# EE464_SCH.net
KiCad netlist of a schematic drawn in Altium Designer
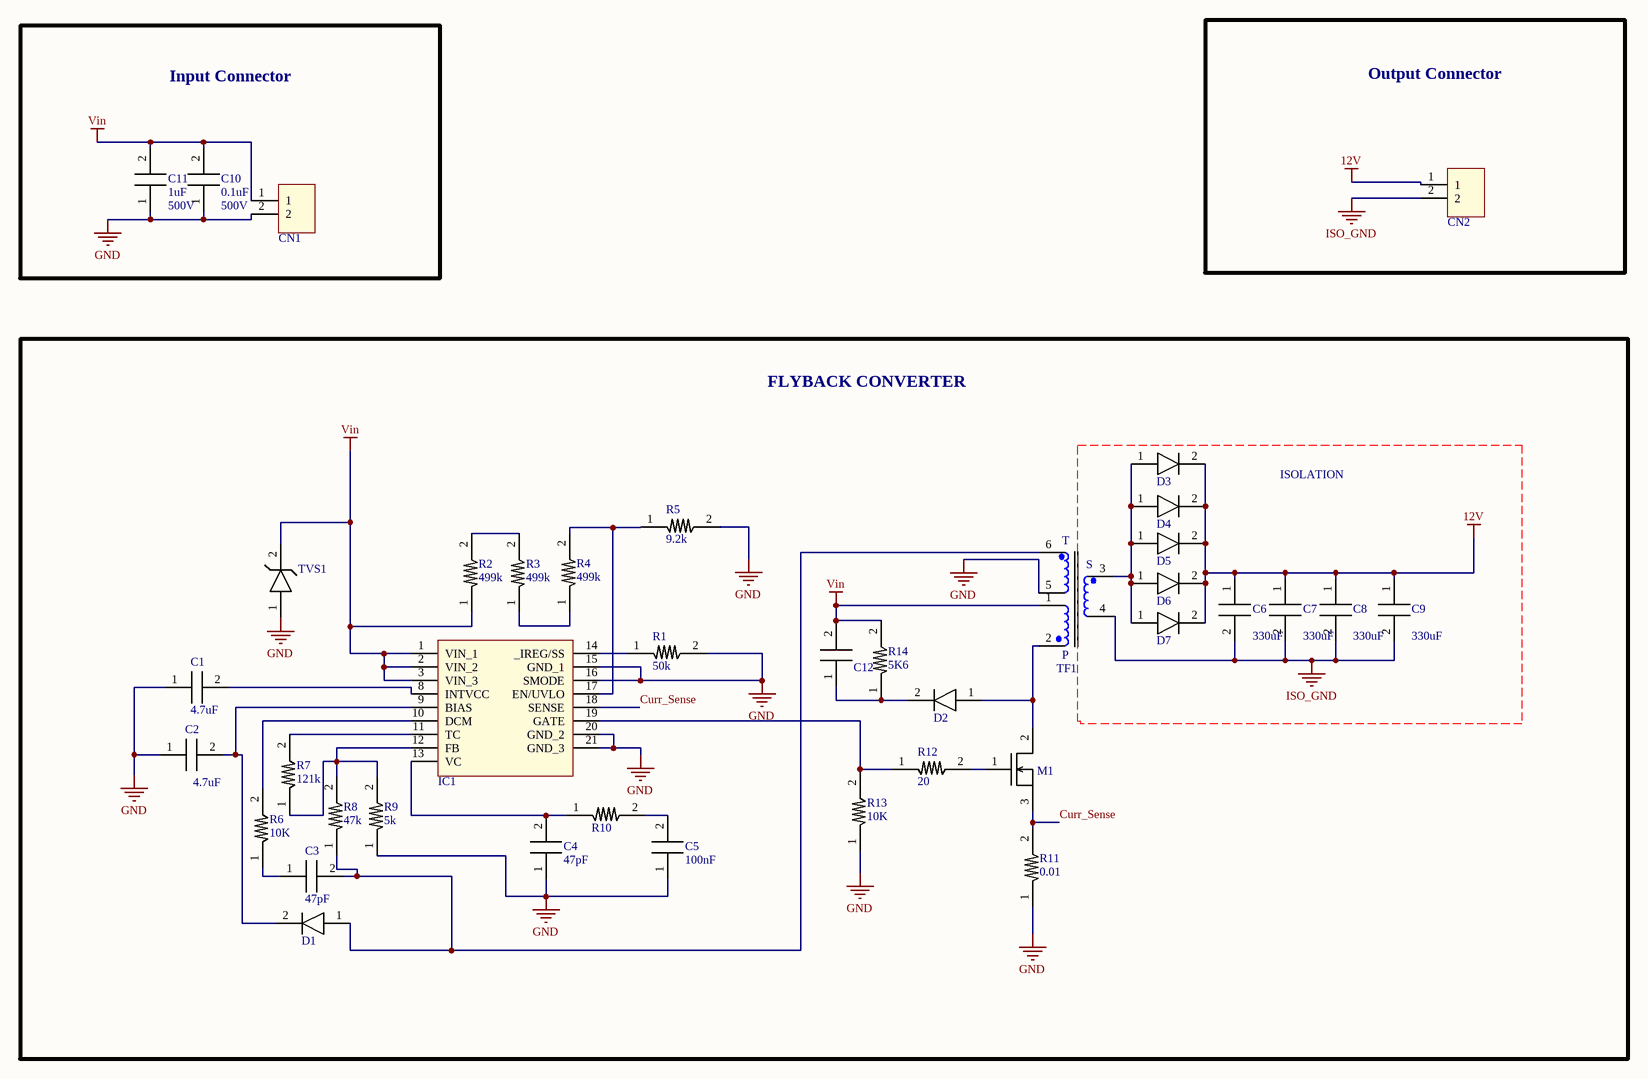
[diagram p0: EE464_SCH.SchDoc]

(export (version "E")
  (design (tool "Eeschema 10.0.6"))
  (components
    (comp (ref "C1")
      (value "CAP 4.7uF 1206")
      (footprint "CAP_1206")
      (fields (field (name "PARAMETER 1") "4.7uF"))
      (libsource (lib "Schlib1") (part "CAP 4.7uF 1206"))
    )
    (comp (ref "C2")
      (value "CAP 4.7uF 1206")
      (footprint "CAP_1206")
      (fields (field (name "PARAMETER 1") "4.7uF"))
      (libsource (lib "Schlib1") (part "CAP 4.7uF 1206"))
    )
    (comp (ref "C3")
      (value "CAP 47pF 0603")
      (footprint "0603_CAP")
      (fields (field (name "PARAMETER 1") "47pF"))
      (libsource (lib "Schlib1") (part "CAP 47pF 0603"))
    )
    (comp (ref "C4")
      (value "CAP 47pF 0603")
      (footprint "0603_CAP")
      (fields (field (name "PARAMETER 1") "47pF"))
      (libsource (lib "Schlib1") (part "CAP 47pF 0603"))
    )
    (comp (ref "C5")
      (value "CAP 100nF")
      (footprint "0603_CAP")
      (fields (field (name "PARAMETER 1") "100nF"))
      (libsource (lib "Schlib1") (part "CAP 100nF"))
    )
    (comp (ref "C6")
      (value "A750KK337M1CAAE014")
      (footprint "CAPPRD350W65D800H900")
      (description "CAP,330uF,AL.POLY.,16V, A750KK337M1CAAE014")
      (fields (field (name "PARAMETER 1") "330uF"))
      (libsource (lib "Schlib1") (part "CAP 330uF AL. POLY."))
    )
    (comp (ref "C7")
      (value "A750KK337M1CAAE014")
      (footprint "CAPPRD350W65D800H900")
      (description "CAP,330uF,AL.POLY.,16V, A750KK337M1CAAE014")
      (fields (field (name "PARAMETER 1") "330uF"))
      (libsource (lib "Schlib1") (part "CAP 330uF AL. POLY."))
    )
    (comp (ref "C8")
      (value "A750KK337M1CAAE014")
      (footprint "CAPPRD350W65D800H900")
      (description "CAP,330uF,AL.POLY.,16V, A750KK337M1CAAE014")
      (fields (field (name "PARAMETER 1") "330uF"))
      (libsource (lib "Schlib1") (part "CAP 330uF AL. POLY."))
    )
    (comp (ref "C9")
      (value "A750KK337M1CAAE014")
      (footprint "CAPPRD350W65D800H900")
      (description "CAP,330uF,AL.POLY.,16V, A750KK337M1CAAE014")
      (fields (field (name "PARAMETER 1") "330uF"))
      (libsource (lib "Schlib1") (part "CAP 330uF AL. POLY."))
    )
    (comp (ref "C10")
      (value "CAP 0.1uF 500V 1210")
      (footprint "CAP_1210")
      (fields (field (name "PARAMETER 1") "0.1uF") (field (name "PARAMETER 2") "500V"))
      (libsource (lib "Schlib1") (part "CAP 0.1uF 500V 1210"))
    )
    (comp (ref "C11")
      (value "CAP 1uF 500v")
      (footprint "CAP_2210")
      (fields (field (name "PARAMETER 1") "1uF") (field (name "PARAMETER 2") "500V"))
      (libsource (lib "Schlib1") (part "CAP 1uF 500v"))
    )
    (comp (ref "C12")
      (value "CAP, 0.1u, 200V, 1206")
      (footprint "CAP_1206")
      (libsource (lib "Schlib1") (part "CAP, 0.1u, 200V, 1206"))
    )
    (comp (ref "CN1")
      (value "CONN_KLE_2_HV")
      (footprint "2828582")
      (libsource (lib "Schlib1") (part "CONN_KLE_2_HV"))
    )
    (comp (ref "CN2")
      (value "CONN_KLE_2_LV")
      (footprint "691103110002")
      (libsource (lib "Schlib1") (part "CONN_KLE_2_LV"))
    )
    (comp (ref "D1")
      (value "DI SK115")
      (footprint "DIOM5227X270N")
      (description "DI, SK115, 150V, 1A, SMA")
      (libsource (lib "Schlib1") (part "DI SK115"))
    )
    (comp (ref "D2")
      (value "DI S1J-E3/61T 600V 1A SMA")
      (footprint "DIOM5227X270N")
      (libsource (lib "Schlib1") (part "DI S1J-E3/61T 600V 1A SMA"))
    )
    (comp (ref "D3")
      (value "DI CDBB3150-HF 150V 3A SMB")
      (footprint "S2GTR")
      (libsource (lib "Schlib1") (part "DI CDBB3150-HF 150V 3A SMB"))
    )
    (comp (ref "D4")
      (value "DI CDBB3150-HF 150V 3A SMB")
      (footprint "S2GTR")
      (libsource (lib "Schlib1") (part "DI CDBB3150-HF 150V 3A SMB"))
    )
    (comp (ref "D5")
      (value "DI CDBB3150-HF 150V 3A SMB")
      (footprint "S2GTR")
      (libsource (lib "Schlib1") (part "DI CDBB3150-HF 150V 3A SMB"))
    )
    (comp (ref "D6")
      (value "DI CDBB3150-HF 150V 3A SMB")
      (footprint "S2GTR")
      (libsource (lib "Schlib1") (part "DI CDBB3150-HF 150V 3A SMB"))
    )
    (comp (ref "D7")
      (value "DI CDBB3150-HF 150V 3A SMB")
      (footprint "S2GTR")
      (libsource (lib "Schlib1") (part "DI CDBB3150-HF 150V 3A SMB"))
    )
    (comp (ref "IC1")
      (value "IC LT8316EFEPB")
      (footprint "LT8316IFEPBF")
      (description "IC, PMIC, Flyback Controller, 16-600V, 100W")
      (libsource (lib "Schlib1") (part "IC LT8316EFEPB"))
    )
    (comp (ref "M1")
      (value "MOS, N-CH, IPD50R500CEAUMA1")
      (footprint "FDD5N50NZ")
      (libsource (lib "Schlib1") (part "MOS, N-CH, IPD50R500CEAUMA1"))
    )
    (comp (ref "R1")
      (value "RES, 50K, 1206")
      (footprint "RES_1206")
      (fields (field (name "PARAMETER 1") "50k"))
      (libsource (lib "Schlib1") (part "RES, 50K, 1206"))
    )
    (comp (ref "R2")
      (value "RES, 499K, 1206")
      (footprint "RES_1206")
      (fields (field (name "PARAMETER 1") "499k"))
      (libsource (lib "Schlib1") (part "RES, 499K, 1206"))
    )
    (comp (ref "R3")
      (value "RES, 499K, 1206")
      (footprint "RES_1206")
      (fields (field (name "PARAMETER 1") "499k"))
      (libsource (lib "Schlib1") (part "RES, 499K, 1206"))
    )
    (comp (ref "R4")
      (value "RES, 499K, 1206")
      (footprint "RES_1206")
      (fields (field (name "PARAMETER 1") "499k"))
      (libsource (lib "Schlib1") (part "RES, 499K, 1206"))
    )
    (comp (ref "R5")
      (value "RES, 9.2K, 0603")
      (footprint "0603_RES")
      (fields (field (name "PARAMETER 1") "9.2k"))
      (libsource (lib "Schlib1") (part "RES, 9.2K, 0603"))
    )
    (comp (ref "R6")
      (value "RES, 10K, 0603")
      (footprint "0603_RES")
      (fields (field (name "PARAMETER 1") "10K"))
      (libsource (lib "Schlib1") (part "RES, 10K, 0603"))
    )
    (comp (ref "R7")
      (value "RES, 121K, 0603")
      (footprint "0603_RES")
      (fields (field (name "PARAMETER 1") "121k"))
      (libsource (lib "Schlib1") (part "RES, 121K, 0603"))
    )
    (comp (ref "R8")
      (value "RES, 47K, 0603")
      (footprint "0603_RES")
      (fields (field (name "PARAMETER 1") "47k"))
      (libsource (lib "Schlib1") (part "RES, 47K, 0603"))
    )
    (comp (ref "R9")
      (value "RES, 5K, 0805")
      (footprint "RES_0805")
      (fields (field (name "PARAMETER 1") "5k"))
      (libsource (lib "Schlib1") (part "RES, 5K, 0805"))
    )
    (comp (ref "R10")
      (value "RES, 15K, 0603")
      (footprint "0603_RES")
      (libsource (lib "Schlib1") (part "RES, 15K, 0603"))
    )
    (comp (ref "R11")
      (value "RES, 0.01,1206")
      (footprint "RES_1206")
      (fields (field (name "PARAMETER 1") "0.01"))
      (libsource (lib "Schlib1") (part "RES, 0.01,1206"))
    )
    (comp (ref "R12")
      (value "RES, 20, 0603")
      (footprint "0603_RES")
      (fields (field (name "PARAMETER 1") "20"))
      (libsource (lib "Schlib1") (part "RES, 20, 0603"))
    )
    (comp (ref "R13")
      (value "RES, 10K, 0603")
      (footprint "0603_RES")
      (fields (field (name "PARAMETER 1") "10K"))
      (libsource (lib "Schlib1") (part "RES, 10K, 0603"))
    )
    (comp (ref "R14")
      (value "RES, 5K6, 0603")
      (footprint "0603_RES")
      (fields (field (name "PARAMETER 1") "5K6"))
      (libsource (lib "Schlib1") (part "RES, 5K6, 0603"))
    )
    (comp (ref "TF1")
      (value "TF 4:1")
      (footprint "tf_mount")
      (libsource (lib "Schlib1") (part "TF 4{colon}1"))
    )
    (comp (ref "TVS1")
      (value "TVS DI SMBJE400CA 400V SMB")
      (footprint "S2GTR")
      (libsource (lib "Schlib1") (part "TVS DI SMBJE400CA 400V SMB"))
    )
  )
  (nets
    (net (code "1") (name "/Curr_Sense") (class "Default")
      (node (ref "IC1") (pin "18") (pinfunction "SENSE_18") (pintype "passive"))
      (node (ref "M1") (pin "3") (pinfunction "3_3") (pintype "passive"))
      (node (ref "R11") (pin "2") (pinfunction "2_2") (pintype "passive"))
    )
    (net (code "2") (name "12V") (class "Default")
      (node (ref "C6") (pin "1") (pinfunction "1_1") (pintype "passive"))
      (node (ref "C7") (pin "1") (pinfunction "1_1") (pintype "passive"))
      (node (ref "C8") (pin "1") (pinfunction "1_1") (pintype "passive"))
      (node (ref "C9") (pin "1") (pinfunction "1_1") (pintype "passive"))
      (node (ref "CN2") (pin "1") (pinfunction "1_1") (pintype "passive"))
      (node (ref "D3") (pin "2") (pinfunction "Cathode_2") (pintype "passive"))
      (node (ref "D4") (pin "2") (pinfunction "Cathode_2") (pintype "passive"))
      (node (ref "D5") (pin "2") (pinfunction "Cathode_2") (pintype "passive"))
      (node (ref "D6") (pin "2") (pinfunction "Cathode_2") (pintype "passive"))
      (node (ref "D7") (pin "2") (pinfunction "Cathode_2") (pintype "passive"))
    )
    (net (code "3") (name "GND") (class "Default")
      (node (ref "C1") (pin "1") (pinfunction "1_1") (pintype "passive"))
      (node (ref "C10") (pin "1") (pinfunction "1_1") (pintype "passive"))
      (node (ref "C11") (pin "1") (pinfunction "1_1") (pintype "passive"))
      (node (ref "C2") (pin "1") (pinfunction "1_1") (pintype "passive"))
      (node (ref "C4") (pin "1") (pinfunction "1_1") (pintype "passive"))
      (node (ref "C5") (pin "1") (pinfunction "1_1") (pintype "passive"))
      (node (ref "CN1") (pin "2") (pinfunction "2_2") (pintype "passive"))
      (node (ref "IC1") (pin "15") (pinfunction "GND_1_15") (pintype "passive"))
      (node (ref "IC1") (pin "16") (pinfunction "SMODE_16") (pintype "passive"))
      (node (ref "IC1") (pin "20") (pinfunction "GND_2_20") (pintype "passive"))
      (node (ref "IC1") (pin "21") (pinfunction "GND_3_21") (pintype "passive"))
      (node (ref "R1") (pin "2") (pinfunction "2_2") (pintype "passive"))
      (node (ref "R11") (pin "1") (pinfunction "1_1") (pintype "passive"))
      (node (ref "R13") (pin "1") (pinfunction "1_1") (pintype "passive"))
      (node (ref "R5") (pin "2") (pinfunction "2_2") (pintype "passive"))
      (node (ref "R9") (pin "1") (pinfunction "1_1") (pintype "passive"))
      (node (ref "TF1") (pin "5") (pinfunction "5_5") (pintype "passive"))
      (node (ref "TVS1") (pin "1") (pinfunction "Anode_1") (pintype "passive"))
    )
    (net (code "4") (name "ISO_GND") (class "Default")
      (node (ref "C6") (pin "2") (pinfunction "2_2") (pintype "passive"))
      (node (ref "C7") (pin "2") (pinfunction "2_2") (pintype "passive"))
      (node (ref "C8") (pin "2") (pinfunction "2_2") (pintype "passive"))
      (node (ref "C9") (pin "2") (pinfunction "2_2") (pintype "passive"))
      (node (ref "CN2") (pin "2") (pinfunction "2_2") (pintype "passive"))
      (node (ref "TF1") (pin "4") (pinfunction "4_4") (pintype "passive"))
    )
    (net (code "5") (name "Net-(C3-Pad1)") (class "Default")
      (node (ref "C3") (pin "1") (pinfunction "1_1") (pintype "passive"))
      (node (ref "R6") (pin "1") (pinfunction "1_1") (pintype "passive"))
    )
    (net (code "6") (name "Net-(C5-Pad2)") (class "Default")
      (node (ref "C5") (pin "2") (pinfunction "2_2") (pintype "passive"))
      (node (ref "R10") (pin "2") (pinfunction "2_2") (pintype "passive"))
    )
    (net (code "7") (name "Net-(D1-Anode)") (class "Default")
      (node (ref "C3") (pin "2") (pinfunction "2_2") (pintype "passive"))
      (node (ref "D1") (pin "1") (pinfunction "Anode_1") (pintype "passive"))
      (node (ref "R8") (pin "1") (pinfunction "1_1") (pintype "passive"))
      (node (ref "TF1") (pin "6") (pinfunction "6_6") (pintype "passive"))
    )
    (net (code "8") (name "Net-(D1-Cathode)") (class "Default")
      (node (ref "C2") (pin "2") (pinfunction "2_2") (pintype "passive"))
      (node (ref "D1") (pin "2") (pinfunction "Cathode_2") (pintype "passive"))
      (node (ref "IC1") (pin "9") (pinfunction "BIAS_9") (pintype "passive"))
    )
    (net (code "9") (name "Net-(D2-Anode)") (class "Default")
      (node (ref "D2") (pin "1") (pinfunction "Anode_1") (pintype "passive"))
      (node (ref "M1") (pin "2") (pinfunction "2_2") (pintype "passive"))
      (node (ref "TF1") (pin "2") (pinfunction "2_2") (pintype "passive"))
    )
    (net (code "10") (name "Net-(D2-Cathode)") (class "Default")
      (node (ref "C12") (pin "1") (pinfunction "1_1") (pintype "passive"))
      (node (ref "D2") (pin "2") (pinfunction "Cathode_2") (pintype "passive"))
      (node (ref "R14") (pin "1") (pinfunction "1_1") (pintype "passive"))
    )
    (net (code "11") (name "Net-(D3-Anode)") (class "Default")
      (node (ref "D3") (pin "1") (pinfunction "Anode_1") (pintype "passive"))
      (node (ref "D4") (pin "1") (pinfunction "Anode_1") (pintype "passive"))
      (node (ref "D5") (pin "1") (pinfunction "Anode_1") (pintype "passive"))
      (node (ref "D6") (pin "1") (pinfunction "Anode_1") (pintype "passive"))
      (node (ref "D7") (pin "1") (pinfunction "Anode_1") (pintype "passive"))
      (node (ref "TF1") (pin "3") (pinfunction "3_3") (pintype "passive"))
    )
    (net (code "12") (name "Net-(IC1-DCM)") (class "Default")
      (node (ref "IC1") (pin "10") (pinfunction "DCM_10") (pintype "passive"))
      (node (ref "R6") (pin "2") (pinfunction "2_2") (pintype "passive"))
    )
    (net (code "13") (name "Net-(IC1-EN{slash}UVLO)") (class "Default")
      (node (ref "IC1") (pin "17") (pinfunction "EN/UVLO_17") (pintype "passive"))
      (node (ref "R4") (pin "2") (pinfunction "2_2") (pintype "passive"))
      (node (ref "R5") (pin "1") (pinfunction "1_1") (pintype "passive"))
    )
    (net (code "14") (name "Net-(IC1-FB)") (class "Default")
      (node (ref "IC1") (pin "12") (pinfunction "FB_12") (pintype "passive"))
      (node (ref "R7") (pin "1") (pinfunction "1_1") (pintype "passive"))
      (node (ref "R8") (pin "2") (pinfunction "2_2") (pintype "passive"))
      (node (ref "R9") (pin "2") (pinfunction "2_2") (pintype "passive"))
    )
    (net (code "15") (name "Net-(IC1-GATE)") (class "Default")
      (node (ref "IC1") (pin "19") (pinfunction "GATE_19") (pintype "passive"))
      (node (ref "R12") (pin "1") (pinfunction "1_1") (pintype "passive"))
      (node (ref "R13") (pin "2") (pinfunction "2_2") (pintype "passive"))
    )
    (net (code "16") (name "Net-(IC1-INTVCC)") (class "Default")
      (node (ref "C1") (pin "2") (pinfunction "2_2") (pintype "passive"))
      (node (ref "IC1") (pin "8") (pinfunction "INTVCC_8") (pintype "passive"))
    )
    (net (code "17") (name "Net-(IC1-TC)") (class "Default")
      (node (ref "IC1") (pin "11") (pinfunction "TC_11") (pintype "passive"))
      (node (ref "R7") (pin "2") (pinfunction "2_2") (pintype "passive"))
    )
    (net (code "18") (name "Net-(IC1-VC)") (class "Default")
      (node (ref "C4") (pin "2") (pinfunction "2_2") (pintype "passive"))
      (node (ref "IC1") (pin "13") (pinfunction "VC_13") (pintype "passive"))
      (node (ref "R10") (pin "1") (pinfunction "1_1") (pintype "passive"))
    )
    (net (code "19") (name "Net-(IC1-_IREG{slash}SS)") (class "Default")
      (node (ref "IC1") (pin "14") (pinfunction "_IREG/SS_14") (pintype "passive"))
      (node (ref "R1") (pin "1") (pinfunction "1_1") (pintype "passive"))
    )
    (net (code "20") (name "Net-(M1-Pad1)") (class "Default")
      (node (ref "M1") (pin "1") (pinfunction "1_1") (pintype "passive"))
      (node (ref "R12") (pin "2") (pinfunction "2_2") (pintype "passive"))
    )
    (net (code "21") (name "Net-(R2-Pad2)") (class "Default")
      (node (ref "R2") (pin "2") (pinfunction "2_2") (pintype "passive"))
      (node (ref "R3") (pin "2") (pinfunction "2_2") (pintype "passive"))
    )
    (net (code "22") (name "Net-(R3-Pad1)") (class "Default")
      (node (ref "R3") (pin "1") (pinfunction "1_1") (pintype "passive"))
      (node (ref "R4") (pin "1") (pinfunction "1_1") (pintype "passive"))
    )
    (net (code "23") (name "Vin") (class "Default")
      (node (ref "C10") (pin "2") (pinfunction "2_2") (pintype "passive"))
      (node (ref "C11") (pin "2") (pinfunction "2_2") (pintype "passive"))
      (node (ref "C12") (pin "2") (pinfunction "2_2") (pintype "passive"))
      (node (ref "CN1") (pin "1") (pinfunction "1_1") (pintype "passive"))
      (node (ref "IC1") (pin "1") (pinfunction "VIN_1_1") (pintype "passive"))
      (node (ref "IC1") (pin "2") (pinfunction "VIN_2_2") (pintype "passive"))
      (node (ref "IC1") (pin "3") (pinfunction "VIN_3_3") (pintype "passive"))
      (node (ref "R14") (pin "2") (pinfunction "2_2") (pintype "passive"))
      (node (ref "R2") (pin "1") (pinfunction "1_1") (pintype "passive"))
      (node (ref "TF1") (pin "1") (pinfunction "1_1") (pintype "passive"))
      (node (ref "TVS1") (pin "2") (pinfunction "Cathode_2") (pintype "passive"))
    )
  )
)
